# AudioProcessor.net
KiCad netlist of a schematic drawn in EAGLE
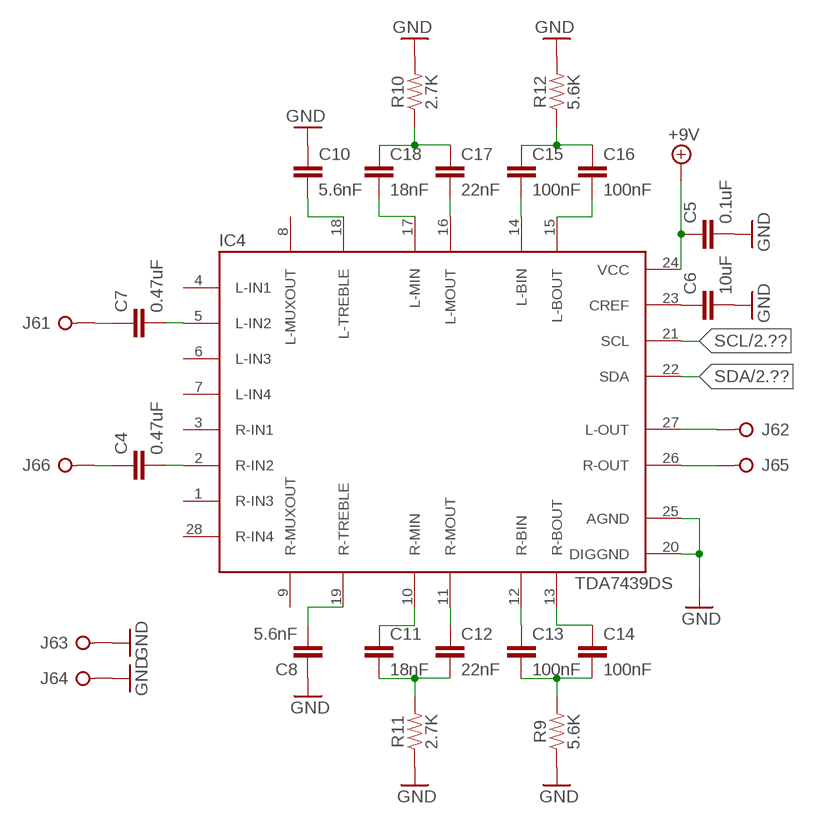
[diagram p0: schematic, sheet 1]
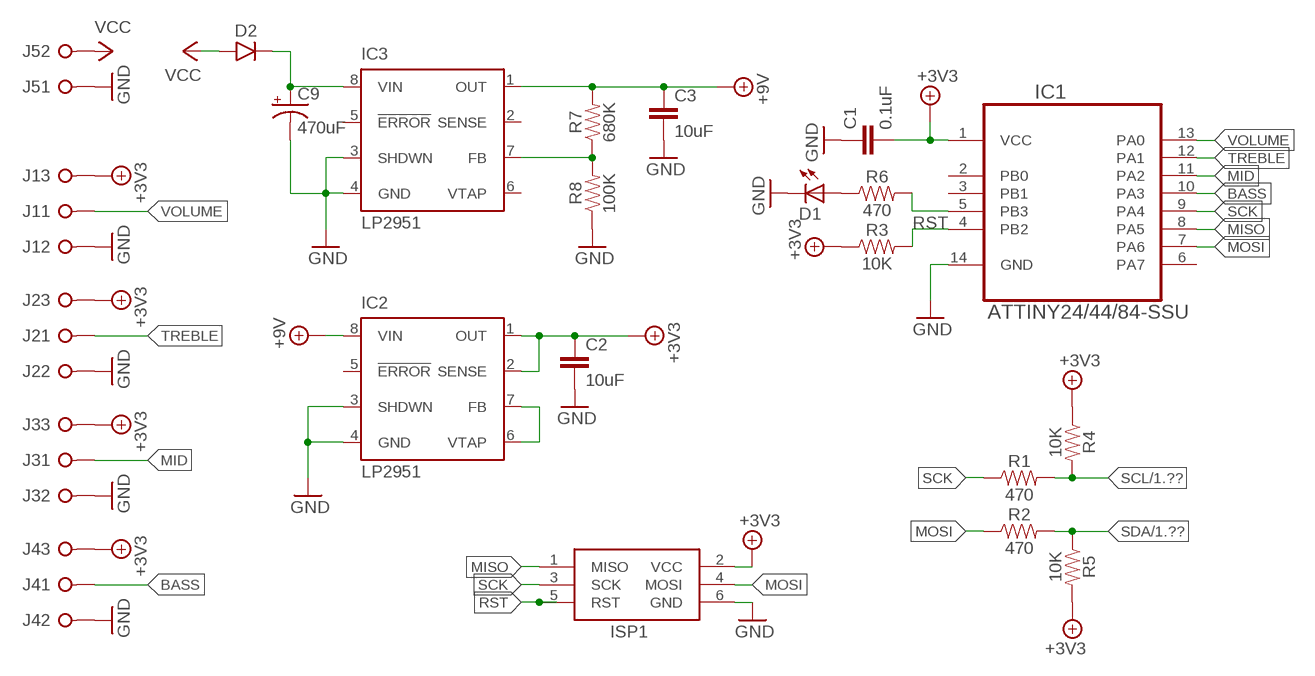
[diagram p1: schematic, sheet 2]

(export (version "E")
  (design (tool "Eeschema 10.0.6"))
  (components
    (comp (ref "C4")
      (value "0.47uF")
      (footprint "eagle-import:CAPACITOR-5MM")
      (libsource (lib "eagle-import") (part "CAPACITOR-5MM"))
    )
    (comp (ref "C5")
      (value "0.1uF")
      (footprint "eagle-import:CAPACITOR-0603")
      (libsource (lib "eagle-import") (part "CAPACITOR-0603"))
    )
    (comp (ref "C6")
      (value "10uF")
      (footprint "eagle-import:CAPACITOR-1206")
      (libsource (lib "eagle-import") (part "CAPACITOR-1206"))
    )
    (comp (ref "C7")
      (value "0.47uF")
      (footprint "eagle-import:CAPACITOR-5MM")
      (libsource (lib "eagle-import") (part "CAPACITOR-5MM"))
    )
    (comp (ref "C8")
      (value "5.6nF")
      (footprint "eagle-import:CAPACITOR-5MM")
      (libsource (lib "eagle-import") (part "CAPACITOR-5MM"))
    )
    (comp (ref "C10")
      (value "5.6nF")
      (footprint "eagle-import:CAPACITOR-5MM")
      (libsource (lib "eagle-import") (part "CAPACITOR-5MM"))
    )
    (comp (ref "C11")
      (value "18nF")
      (footprint "eagle-import:CAPACITOR-5MM")
      (libsource (lib "eagle-import") (part "CAPACITOR-5MM"))
    )
    (comp (ref "C12")
      (value "22nF")
      (footprint "eagle-import:CAPACITOR-5MM")
      (libsource (lib "eagle-import") (part "CAPACITOR-5MM"))
    )
    (comp (ref "C13")
      (value "100nF")
      (footprint "eagle-import:CAPACITOR-5MM")
      (libsource (lib "eagle-import") (part "CAPACITOR-5MM"))
    )
    (comp (ref "C14")
      (value "100nF")
      (footprint "eagle-import:CAPACITOR-5MM")
      (libsource (lib "eagle-import") (part "CAPACITOR-5MM"))
    )
    (comp (ref "C15")
      (value "100nF")
      (footprint "eagle-import:CAPACITOR-5MM")
      (libsource (lib "eagle-import") (part "CAPACITOR-5MM"))
    )
    (comp (ref "C16")
      (value "100nF")
      (footprint "eagle-import:CAPACITOR-5MM")
      (libsource (lib "eagle-import") (part "CAPACITOR-5MM"))
    )
    (comp (ref "C17")
      (value "22nF")
      (footprint "eagle-import:CAPACITOR-5MM")
      (libsource (lib "eagle-import") (part "CAPACITOR-5MM"))
    )
    (comp (ref "C18")
      (value "18nF")
      (footprint "eagle-import:CAPACITOR-5MM")
      (libsource (lib "eagle-import") (part "CAPACITOR-5MM"))
    )
    (comp (ref "IC4")
      (value "TDA7439DS")
      (footprint "eagle-import:SO-28W")
      (libsource (lib "eagle-import") (part "TDA7439DS"))
    )
    (comp (ref "J6")
      (value "PINHD-1X6-JST-PH")
      (footprint "eagle-import:JST-B6B-PH")
      (libsource (lib "eagle-import") (part "PINHD-1X6-JST-PH"))
    )
    (comp (ref "R9")
      (value "5.6K")
      (footprint "eagle-import:RESISTOR-0805")
      (libsource (lib "eagle-import") (part "RESISTOR-0805"))
    )
    (comp (ref "R10")
      (value "2.7K")
      (footprint "eagle-import:RESISTOR-0805")
      (libsource (lib "eagle-import") (part "RESISTOR-0805"))
    )
    (comp (ref "R11")
      (value "2.7K")
      (footprint "eagle-import:RESISTOR-0805")
      (libsource (lib "eagle-import") (part "RESISTOR-0805"))
    )
    (comp (ref "R12")
      (value "5.6K")
      (footprint "eagle-import:RESISTOR-0805")
      (libsource (lib "eagle-import") (part "RESISTOR-0805"))
    )
    (comp (ref "C1")
      (value "0.1uF")
      (footprint "eagle-import:CAPACITOR-0603")
      (libsource (lib "eagle-import") (part "CAPACITOR-0603"))
    )
    (comp (ref "C2")
      (value "10uF")
      (footprint "eagle-import:CAPACITOR-1206")
      (libsource (lib "eagle-import") (part "CAPACITOR-1206"))
    )
    (comp (ref "C3")
      (value "10uF")
      (footprint "eagle-import:CAPACITOR-1206")
      (libsource (lib "eagle-import") (part "CAPACITOR-1206"))
    )
    (comp (ref "C9")
      (value "470uF")
      (footprint "eagle-import:CAP-POL-3.5-8")
      (libsource (lib "eagle-import") (part "CAPACITOR-POLARIZED-3.5-8"))
    )
    (comp (ref "D1")
      (value "LED-0805")
      (footprint "eagle-import:LED-0805")
      (libsource (lib "eagle-import") (part "LED-0805"))
    )
    (comp (ref "D2")
      (value "DIODE-DO214AC")
      (footprint "eagle-import:DO-214AC")
      (libsource (lib "eagle-import") (part "DIODE-DO214AC"))
    )
    (comp (ref "IC1")
      (value "ATTINY24/44/84-SSU")
      (footprint "eagle-import:SO-14")
      (libsource (lib "eagle-import") (part "ATTINY24/44/84-SSU"))
    )
    (comp (ref "IC2")
      (value "LP2951")
      (footprint "eagle-import:SOIC-08")
      (libsource (lib "eagle-import") (part "LP2951"))
    )
    (comp (ref "IC3")
      (value "LP2951")
      (footprint "eagle-import:SOIC-08")
      (libsource (lib "eagle-import") (part "LP2951"))
    )
    (comp (ref "ISP1")
      (value "ICSP-HEADER-6")
      (footprint "eagle-import:ICSP-HEADER")
      (libsource (lib "eagle-import") (part "ICSP-HEADER-6"))
    )
    (comp (ref "J1")
      (value "PINHD-1X3-JST-PH")
      (footprint "eagle-import:JST-B3B-PH")
      (libsource (lib "eagle-import") (part "PINHD-1X3-JST-PH"))
    )
    (comp (ref "J2")
      (value "PINHD-1X3-JST-PH")
      (footprint "eagle-import:JST-B3B-PH")
      (libsource (lib "eagle-import") (part "PINHD-1X3-JST-PH"))
    )
    (comp (ref "J3")
      (value "PINHD-1X3-JST-PH")
      (footprint "eagle-import:JST-B3B-PH")
      (libsource (lib "eagle-import") (part "PINHD-1X3-JST-PH"))
    )
    (comp (ref "J4")
      (value "PINHD-1X3-JST-PH")
      (footprint "eagle-import:JST-B3B-PH")
      (libsource (lib "eagle-import") (part "PINHD-1X3-JST-PH"))
    )
    (comp (ref "J5")
      (value "PINHD-1X2-JST-PH")
      (footprint "eagle-import:JST-B2B-PH")
      (libsource (lib "eagle-import") (part "PINHD-1X2-JST-PH"))
    )
    (comp (ref "R1")
      (value "470")
      (footprint "eagle-import:RESISTOR-0805")
      (libsource (lib "eagle-import") (part "RESISTOR-0805"))
    )
    (comp (ref "R2")
      (value "470")
      (footprint "eagle-import:RESISTOR-0805")
      (libsource (lib "eagle-import") (part "RESISTOR-0805"))
    )
    (comp (ref "R3")
      (value "10K")
      (footprint "eagle-import:RESISTOR-0805")
      (libsource (lib "eagle-import") (part "RESISTOR-0805"))
    )
    (comp (ref "R4")
      (value "10K")
      (footprint "eagle-import:RESISTOR-0805")
      (libsource (lib "eagle-import") (part "RESISTOR-0805"))
    )
    (comp (ref "R5")
      (value "10K")
      (footprint "eagle-import:RESISTOR-0805")
      (libsource (lib "eagle-import") (part "RESISTOR-0805"))
    )
    (comp (ref "R6")
      (value "470")
      (footprint "eagle-import:RESISTOR-0805")
      (libsource (lib "eagle-import") (part "RESISTOR-0805"))
    )
    (comp (ref "R7")
      (value "680K")
      (footprint "eagle-import:RESISTOR-0805")
      (libsource (lib "eagle-import") (part "RESISTOR-0805"))
    )
    (comp (ref "R8")
      (value "100K")
      (footprint "eagle-import:RESISTOR-0805")
      (libsource (lib "eagle-import") (part "RESISTOR-0805"))
    )
  )
  (nets
    (net (code "1") (name "+3V3") (class "Default")
      (node (ref "C1") (pin "2") (pinfunction "2_2") (pintype "passive"))
      (node (ref "C2") (pin "1") (pinfunction "1_1") (pintype "passive"))
      (node (ref "IC1") (pin "1") (pinfunction "VCC_1") (pintype "power_in"))
      (node (ref "IC2") (pin "1") (pinfunction "OUT_1") (pintype "power_in"))
      (node (ref "IC2") (pin "2") (pinfunction "SENSE_2") (pintype "passive"))
      (node (ref "ISP1") (pin "2") (pinfunction "VCC_2") (pintype "power_in"))
      (node (ref "J1") (pin "3") (pinfunction "KL_3") (pintype "passive"))
      (node (ref "J2") (pin "3") (pinfunction "KL_3") (pintype "passive"))
      (node (ref "J3") (pin "3") (pinfunction "KL_3") (pintype "passive"))
      (node (ref "J4") (pin "3") (pinfunction "KL_3") (pintype "passive"))
      (node (ref "R3") (pin "1") (pinfunction "1_1") (pintype "passive"))
      (node (ref "R4") (pin "1") (pinfunction "1_1") (pintype "passive"))
      (node (ref "R5") (pin "2") (pinfunction "2_2") (pintype "passive"))
    )
    (net (code "2") (name "+9V") (class "Default")
      (node (ref "C3") (pin "1") (pinfunction "1_1") (pintype "passive"))
      (node (ref "C5") (pin "1") (pinfunction "1_1") (pintype "passive"))
      (node (ref "IC2") (pin "8") (pinfunction "VIN_8") (pintype "input"))
      (node (ref "IC3") (pin "1") (pinfunction "OUT_1") (pintype "power_in"))
      (node (ref "IC4") (pin "24") (pinfunction "VCC_24") (pintype "power_in"))
      (node (ref "R7") (pin "2") (pinfunction "2_2") (pintype "passive"))
    )
    (net (code "3") (name "BASS") (class "Default")
      (node (ref "IC1") (pin "10") (pinfunction "PA3_10") (pintype "bidirectional"))
      (node (ref "J4") (pin "1") (pinfunction "KL_1") (pintype "passive"))
    )
    (net (code "4") (name "GND") (class "Default")
      (node (ref "C1") (pin "1") (pinfunction "1_1") (pintype "passive"))
      (node (ref "C10") (pin "1") (pinfunction "1_1") (pintype "passive"))
      (node (ref "C2") (pin "2") (pinfunction "2_2") (pintype "passive"))
      (node (ref "C3") (pin "2") (pinfunction "2_2") (pintype "passive"))
      (node (ref "C5") (pin "2") (pinfunction "2_2") (pintype "passive"))
      (node (ref "C6") (pin "2") (pinfunction "2_2") (pintype "passive"))
      (node (ref "C8") (pin "1") (pinfunction "1_1") (pintype "passive"))
      (node (ref "C9") (pin "-") (pinfunction "-_-") (pintype "passive"))
      (node (ref "D1") (pin "2") (pinfunction "C_2") (pintype "passive"))
      (node (ref "IC1") (pin "14") (pinfunction "GND_14") (pintype "passive"))
      (node (ref "IC2") (pin "3") (pinfunction "SHDWN_3") (pintype "input"))
      (node (ref "IC2") (pin "4") (pinfunction "GND_4") (pintype "power_in"))
      (node (ref "IC3") (pin "3") (pinfunction "SHDWN_3") (pintype "input"))
      (node (ref "IC3") (pin "4") (pinfunction "GND_4") (pintype "power_in"))
      (node (ref "IC4") (pin "20") (pinfunction "DIGGND_20") (pintype "power_in"))
      (node (ref "IC4") (pin "25") (pinfunction "AGND_25") (pintype "power_in"))
      (node (ref "ISP1") (pin "6") (pinfunction "GND_6") (pintype "power_in"))
      (node (ref "J1") (pin "2") (pinfunction "KL_2") (pintype "passive"))
      (node (ref "J2") (pin "2") (pinfunction "KL_2") (pintype "passive"))
      (node (ref "J3") (pin "2") (pinfunction "KL_2") (pintype "passive"))
      (node (ref "J4") (pin "2") (pinfunction "KL_2") (pintype "passive"))
      (node (ref "J5") (pin "1") (pinfunction "KL_1") (pintype "passive"))
      (node (ref "J6") (pin "3") (pinfunction "KL_3") (pintype "passive"))
      (node (ref "J6") (pin "4") (pinfunction "KL_4") (pintype "passive"))
      (node (ref "R10") (pin "2") (pinfunction "2_2") (pintype "passive"))
      (node (ref "R11") (pin "1") (pinfunction "1_1") (pintype "passive"))
      (node (ref "R12") (pin "2") (pinfunction "2_2") (pintype "passive"))
      (node (ref "R8") (pin "1") (pinfunction "1_1") (pintype "passive"))
      (node (ref "R9") (pin "1") (pinfunction "1_1") (pintype "passive"))
    )
    (net (code "5") (name "MID") (class "Default")
      (node (ref "IC1") (pin "11") (pinfunction "PA2_11") (pintype "bidirectional"))
      (node (ref "J3") (pin "1") (pinfunction "KL_1") (pintype "passive"))
    )
    (net (code "6") (name "MISO") (class "Default")
      (node (ref "IC1") (pin "8") (pinfunction "PA5_8") (pintype "bidirectional"))
      (node (ref "ISP1") (pin "1") (pinfunction "MISO_1") (pintype "input"))
    )
    (net (code "7") (name "MOSI") (class "Default")
      (node (ref "IC1") (pin "7") (pinfunction "PA6_7") (pintype "bidirectional"))
      (node (ref "ISP1") (pin "4") (pinfunction "MOSI_4") (pintype "output"))
      (node (ref "R2") (pin "1") (pinfunction "1_1") (pintype "passive"))
    )
    (net (code "8") (name "Net-(C11-Pad2)") (class "Default")
      (node (ref "C11") (pin "2") (pinfunction "2_2") (pintype "passive"))
      (node (ref "C12") (pin "2") (pinfunction "2_2") (pintype "passive"))
      (node (ref "R11") (pin "2") (pinfunction "2_2") (pintype "passive"))
    )
    (net (code "9") (name "Net-(C13-Pad2)") (class "Default")
      (node (ref "C13") (pin "2") (pinfunction "2_2") (pintype "passive"))
      (node (ref "C14") (pin "2") (pinfunction "2_2") (pintype "passive"))
      (node (ref "R9") (pin "2") (pinfunction "2_2") (pintype "passive"))
    )
    (net (code "10") (name "Net-(C15-Pad1)") (class "Default")
      (node (ref "C15") (pin "1") (pinfunction "1_1") (pintype "passive"))
      (node (ref "C16") (pin "1") (pinfunction "1_1") (pintype "passive"))
      (node (ref "R12") (pin "1") (pinfunction "1_1") (pintype "passive"))
    )
    (net (code "11") (name "Net-(C17-Pad1)") (class "Default")
      (node (ref "C17") (pin "1") (pinfunction "1_1") (pintype "passive"))
      (node (ref "C18") (pin "1") (pinfunction "1_1") (pintype "passive"))
      (node (ref "R10") (pin "1") (pinfunction "1_1") (pintype "passive"))
    )
    (net (code "12") (name "Net-(D1-A)") (class "Default")
      (node (ref "D1") (pin "1") (pinfunction "A_1") (pintype "passive"))
      (node (ref "R6") (pin "1") (pinfunction "1_1") (pintype "passive"))
    )
    (net (code "13") (name "Net-(D2--)") (class "Default")
      (node (ref "C9") (pin "+") (pinfunction "+_+") (pintype "passive"))
      (node (ref "D2") (pin "2") (pinfunction "-_2") (pintype "passive"))
      (node (ref "IC3") (pin "8") (pinfunction "VIN_8") (pintype "input"))
    )
    (net (code "14") (name "Net-(IC1-PB3)") (class "Default")
      (node (ref "IC1") (pin "5") (pinfunction "PB3_5") (pintype "bidirectional"))
      (node (ref "R6") (pin "2") (pinfunction "2_2") (pintype "passive"))
    )
    (net (code "15") (name "Net-(IC2-FB)") (class "Default")
      (node (ref "IC2") (pin "6") (pinfunction "VTAP_6") (pintype "output"))
      (node (ref "IC2") (pin "7") (pinfunction "FB_7") (pintype "input"))
    )
    (net (code "16") (name "Net-(IC3-FB)") (class "Default")
      (node (ref "IC3") (pin "7") (pinfunction "FB_7") (pintype "input"))
      (node (ref "R7") (pin "1") (pinfunction "1_1") (pintype "passive"))
      (node (ref "R8") (pin "2") (pinfunction "2_2") (pintype "passive"))
    )
    (net (code "17") (name "Net-(IC4-CREF)") (class "Default")
      (node (ref "C6") (pin "1") (pinfunction "1_1") (pintype "passive"))
      (node (ref "IC4") (pin "23") (pinfunction "CREF_23") (pintype "bidirectional"))
    )
    (net (code "18") (name "Net-(IC4-L-BIN)") (class "Default")
      (node (ref "C15") (pin "2") (pinfunction "2_2") (pintype "passive"))
      (node (ref "IC4") (pin "14") (pinfunction "L-BIN_14") (pintype "input"))
    )
    (net (code "19") (name "Net-(IC4-L-BOUT)") (class "Default")
      (node (ref "C16") (pin "2") (pinfunction "2_2") (pintype "passive"))
      (node (ref "IC4") (pin "15") (pinfunction "L-BOUT_15") (pintype "output"))
    )
    (net (code "20") (name "Net-(IC4-L-IN2)") (class "Default")
      (node (ref "C7") (pin "2") (pinfunction "2_2") (pintype "passive"))
      (node (ref "IC4") (pin "5") (pinfunction "L-IN2_5") (pintype "passive"))
    )
    (net (code "21") (name "Net-(IC4-L-MIN)") (class "Default")
      (node (ref "C18") (pin "2") (pinfunction "2_2") (pintype "passive"))
      (node (ref "IC4") (pin "17") (pinfunction "L-MIN_17") (pintype "input"))
    )
    (net (code "22") (name "Net-(IC4-L-MOUT)") (class "Default")
      (node (ref "C17") (pin "2") (pinfunction "2_2") (pintype "passive"))
      (node (ref "IC4") (pin "16") (pinfunction "L-MOUT_16") (pintype "output"))
    )
    (net (code "23") (name "Net-(IC4-L-OUT)") (class "Default")
      (node (ref "IC4") (pin "27") (pinfunction "L-OUT_27") (pintype "output"))
      (node (ref "J6") (pin "2") (pinfunction "KL_2") (pintype "passive"))
    )
    (net (code "24") (name "Net-(IC4-L-TREBLE)") (class "Default")
      (node (ref "C10") (pin "2") (pinfunction "2_2") (pintype "passive"))
      (node (ref "IC4") (pin "18") (pinfunction "L-TREBLE_18") (pintype "output"))
    )
    (net (code "25") (name "Net-(IC4-R-BIN)") (class "Default")
      (node (ref "C13") (pin "1") (pinfunction "1_1") (pintype "passive"))
      (node (ref "IC4") (pin "12") (pinfunction "R-BIN_12") (pintype "input"))
    )
    (net (code "26") (name "Net-(IC4-R-BOUT)") (class "Default")
      (node (ref "C14") (pin "1") (pinfunction "1_1") (pintype "passive"))
      (node (ref "IC4") (pin "13") (pinfunction "R-BOUT_13") (pintype "output"))
    )
    (net (code "27") (name "Net-(IC4-R-IN2)") (class "Default")
      (node (ref "C4") (pin "2") (pinfunction "2_2") (pintype "passive"))
      (node (ref "IC4") (pin "2") (pinfunction "R-IN2_2") (pintype "passive"))
    )
    (net (code "28") (name "Net-(IC4-R-MIN)") (class "Default")
      (node (ref "C11") (pin "1") (pinfunction "1_1") (pintype "passive"))
      (node (ref "IC4") (pin "10") (pinfunction "R-MIN_10") (pintype "input"))
    )
    (net (code "29") (name "Net-(IC4-R-MOUT)") (class "Default")
      (node (ref "C12") (pin "1") (pinfunction "1_1") (pintype "passive"))
      (node (ref "IC4") (pin "11") (pinfunction "R-MOUT_11") (pintype "output"))
    )
    (net (code "30") (name "Net-(IC4-R-OUT)") (class "Default")
      (node (ref "IC4") (pin "26") (pinfunction "R-OUT_26") (pintype "output"))
      (node (ref "J6") (pin "5") (pinfunction "KL_5") (pintype "passive"))
    )
    (net (code "31") (name "Net-(IC4-R-TREBLE)") (class "Default")
      (node (ref "C8") (pin "2") (pinfunction "2_2") (pintype "passive"))
      (node (ref "IC4") (pin "19") (pinfunction "R-TREBLE_19") (pintype "output"))
    )
    (net (code "32") (name "Net-(J6A-KL)") (class "Default")
      (node (ref "C7") (pin "1") (pinfunction "1_1") (pintype "passive"))
      (node (ref "J6") (pin "1") (pinfunction "KL_1") (pintype "passive"))
    )
    (net (code "33") (name "Net-(J6F-KL)") (class "Default")
      (node (ref "C4") (pin "1") (pinfunction "1_1") (pintype "passive"))
      (node (ref "J6") (pin "6") (pinfunction "KL_6") (pintype "passive"))
    )
    (net (code "34") (name "RST") (class "Default")
      (node (ref "IC1") (pin "4") (pinfunction "PB2_4") (pintype "bidirectional"))
      (node (ref "ISP1") (pin "5") (pinfunction "RST_5") (pintype "output"))
      (node (ref "R3") (pin "2") (pinfunction "2_2") (pintype "passive"))
    )
    (net (code "35") (name "SCK") (class "Default")
      (node (ref "IC1") (pin "9") (pinfunction "PA4_9") (pintype "bidirectional"))
      (node (ref "ISP1") (pin "3") (pinfunction "SCK_3") (pintype "output"))
      (node (ref "R1") (pin "1") (pinfunction "1_1") (pintype "passive"))
    )
    (net (code "36") (name "SCL") (class "Default")
      (node (ref "IC4") (pin "21") (pinfunction "SCL_21") (pintype "bidirectional"))
      (node (ref "R1") (pin "2") (pinfunction "2_2") (pintype "passive"))
      (node (ref "R4") (pin "2") (pinfunction "2_2") (pintype "passive"))
    )
    (net (code "37") (name "SDA") (class "Default")
      (node (ref "IC4") (pin "22") (pinfunction "SDA_22") (pintype "bidirectional"))
      (node (ref "R2") (pin "2") (pinfunction "2_2") (pintype "passive"))
      (node (ref "R5") (pin "1") (pinfunction "1_1") (pintype "passive"))
    )
    (net (code "38") (name "TREBLE") (class "Default")
      (node (ref "IC1") (pin "12") (pinfunction "PA1_12") (pintype "bidirectional"))
      (node (ref "J2") (pin "1") (pinfunction "KL_1") (pintype "passive"))
    )
    (net (code "39") (name "VCC") (class "Default")
      (node (ref "D2") (pin "1") (pinfunction "+_1") (pintype "passive"))
      (node (ref "J5") (pin "2") (pinfunction "KL_2") (pintype "passive"))
    )
    (net (code "40") (name "VOLUME") (class "Default")
      (node (ref "IC1") (pin "13") (pinfunction "PA0_13") (pintype "bidirectional"))
      (node (ref "J1") (pin "1") (pinfunction "KL_1") (pintype "passive"))
    )
    (net (code "41") (name "unconnected-(IC1-PA7-Pad6)") (class "Default")
      (node (ref "IC1") (pin "6") (pinfunction "PA7_6") (pintype "bidirectional"))
    )
    (net (code "42") (name "unconnected-(IC1-PB0-Pad2)") (class "Default")
      (node (ref "IC1") (pin "2") (pinfunction "PB0_2") (pintype "bidirectional"))
    )
    (net (code "43") (name "unconnected-(IC1-PB1-Pad3)") (class "Default")
      (node (ref "IC1") (pin "3") (pinfunction "PB1_3") (pintype "bidirectional"))
    )
    (net (code "44") (name "unconnected-(IC2-~{ERROR}-Pad5)") (class "Default")
      (node (ref "IC2") (pin "5") (pinfunction "~{ERROR}_5") (pintype "output"))
    )
    (net (code "45") (name "unconnected-(IC3-SENSE-Pad2)") (class "Default")
      (node (ref "IC3") (pin "2") (pinfunction "SENSE_2") (pintype "passive"))
    )
    (net (code "46") (name "unconnected-(IC3-VTAP-Pad6)") (class "Default")
      (node (ref "IC3") (pin "6") (pinfunction "VTAP_6") (pintype "output"))
    )
    (net (code "47") (name "unconnected-(IC3-~{ERROR}-Pad5)") (class "Default")
      (node (ref "IC3") (pin "5") (pinfunction "~{ERROR}_5") (pintype "output"))
    )
    (net (code "48") (name "unconnected-(IC4-L-IN1-Pad4)") (class "Default")
      (node (ref "IC4") (pin "4") (pinfunction "L-IN1_4") (pintype "passive"))
    )
    (net (code "49") (name "unconnected-(IC4-L-IN3-Pad6)") (class "Default")
      (node (ref "IC4") (pin "6") (pinfunction "L-IN3_6") (pintype "passive"))
    )
    (net (code "50") (name "unconnected-(IC4-L-IN4-Pad7)") (class "Default")
      (node (ref "IC4") (pin "7") (pinfunction "L-IN4_7") (pintype "passive"))
    )
    (net (code "51") (name "unconnected-(IC4-L-MUXOUT-Pad8)") (class "Default")
      (node (ref "IC4") (pin "8") (pinfunction "L-MUXOUT_8") (pintype "output"))
    )
    (net (code "52") (name "unconnected-(IC4-R-IN1-Pad3)") (class "Default")
      (node (ref "IC4") (pin "3") (pinfunction "R-IN1_3") (pintype "passive"))
    )
    (net (code "53") (name "unconnected-(IC4-R-IN3-Pad1)") (class "Default")
      (node (ref "IC4") (pin "1") (pinfunction "R-IN3_1") (pintype "passive"))
    )
    (net (code "54") (name "unconnected-(IC4-R-IN4-Pad28)") (class "Default")
      (node (ref "IC4") (pin "28") (pinfunction "R-IN4_28") (pintype "passive"))
    )
    (net (code "55") (name "unconnected-(IC4-R-MUXOUT-Pad9)") (class "Default")
      (node (ref "IC4") (pin "9") (pinfunction "R-MUXOUT_9") (pintype "output"))
    )
  )
)
